# SchematicInkTime.net
KiCad netlist of a schematic drawn in EAGLE
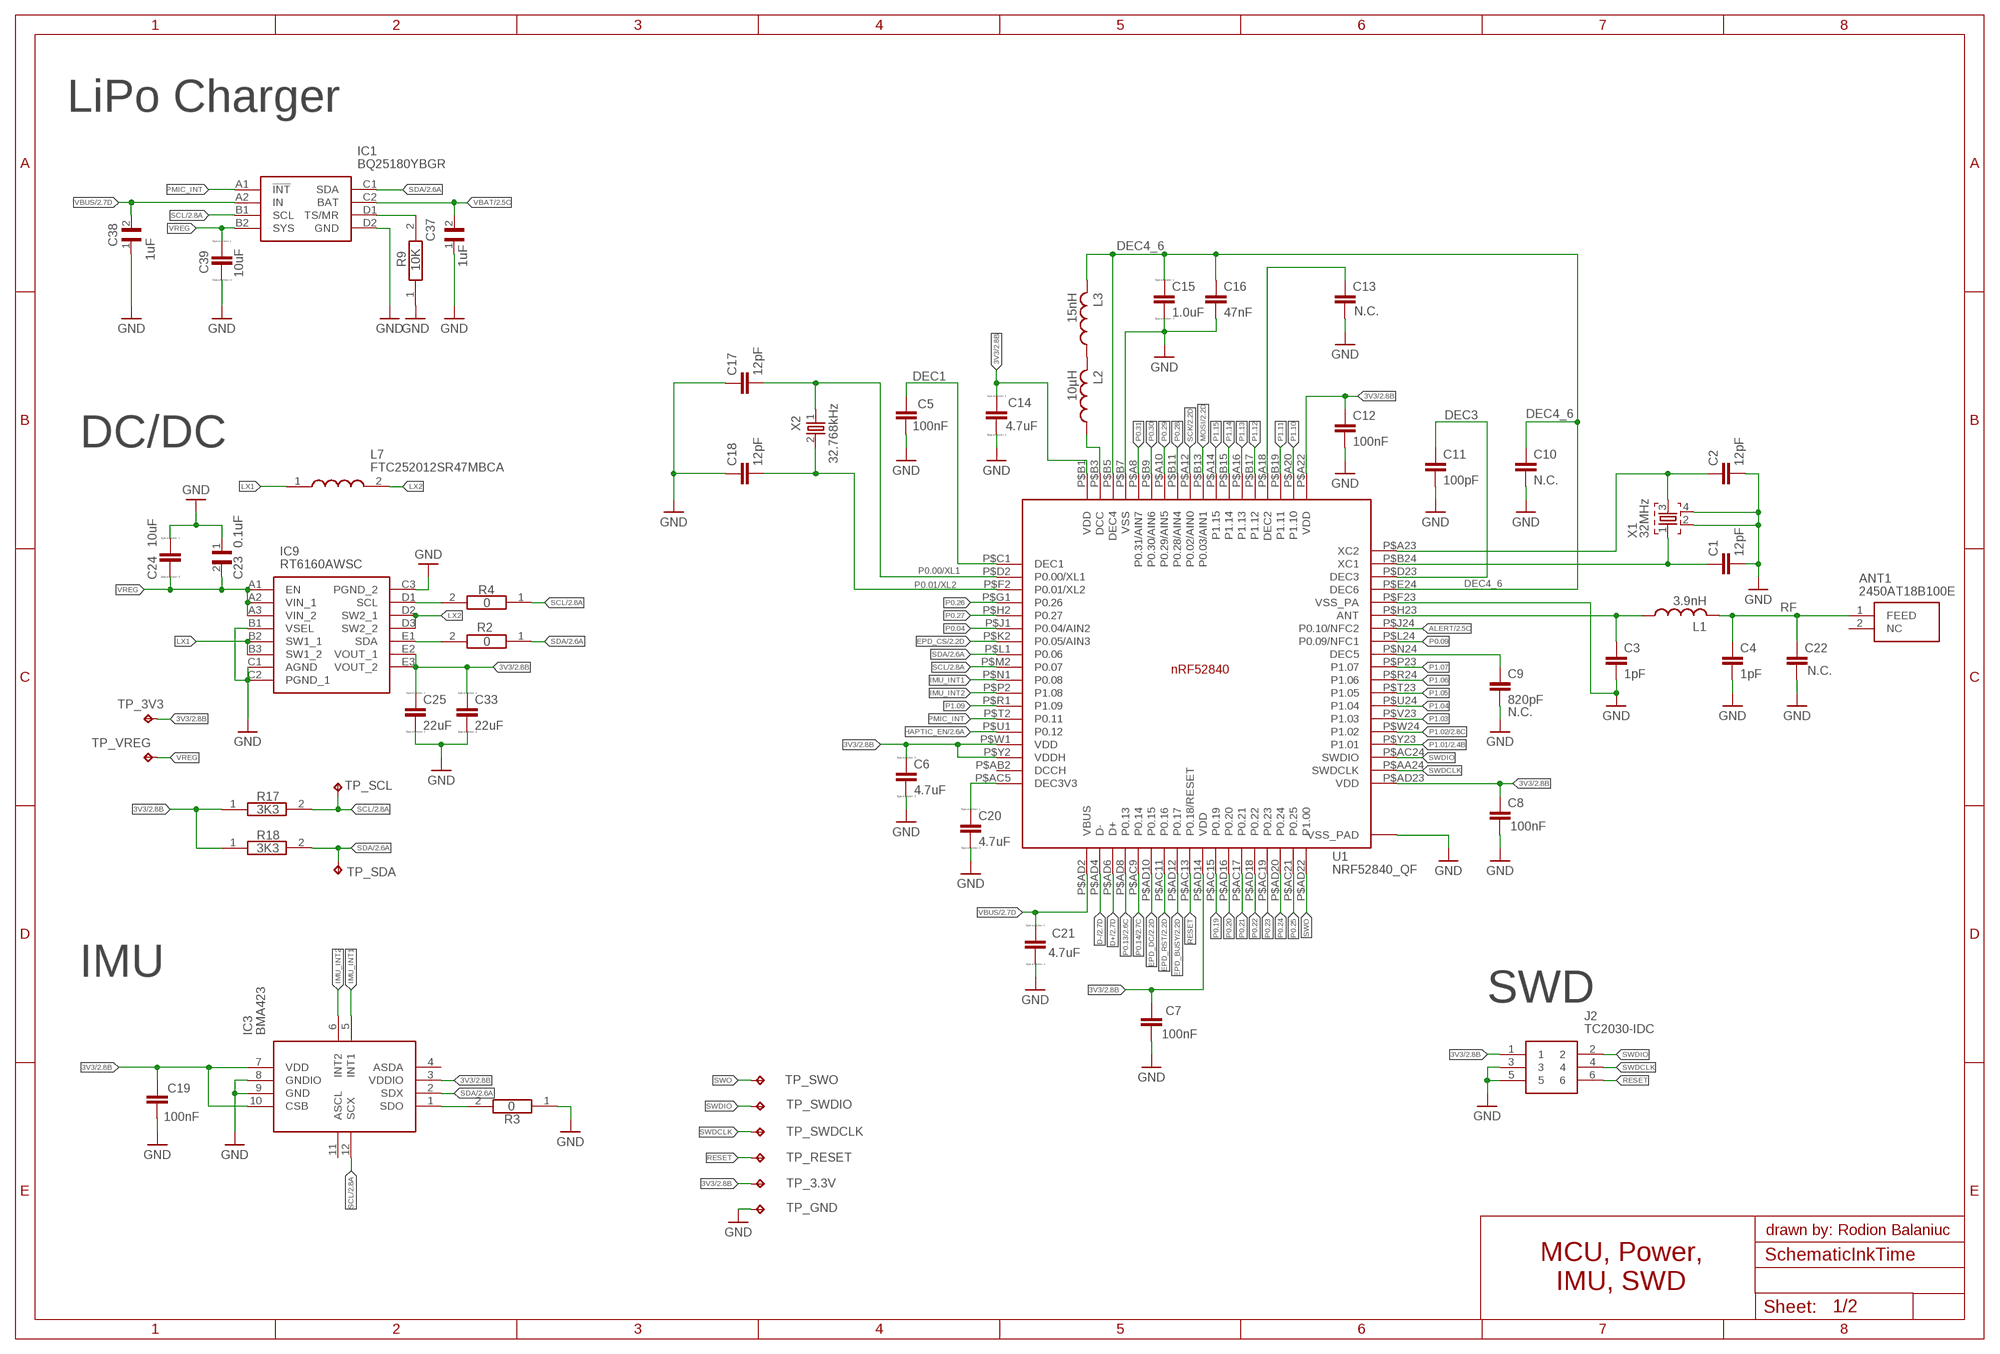
[diagram p0: schematic, sheet 1]
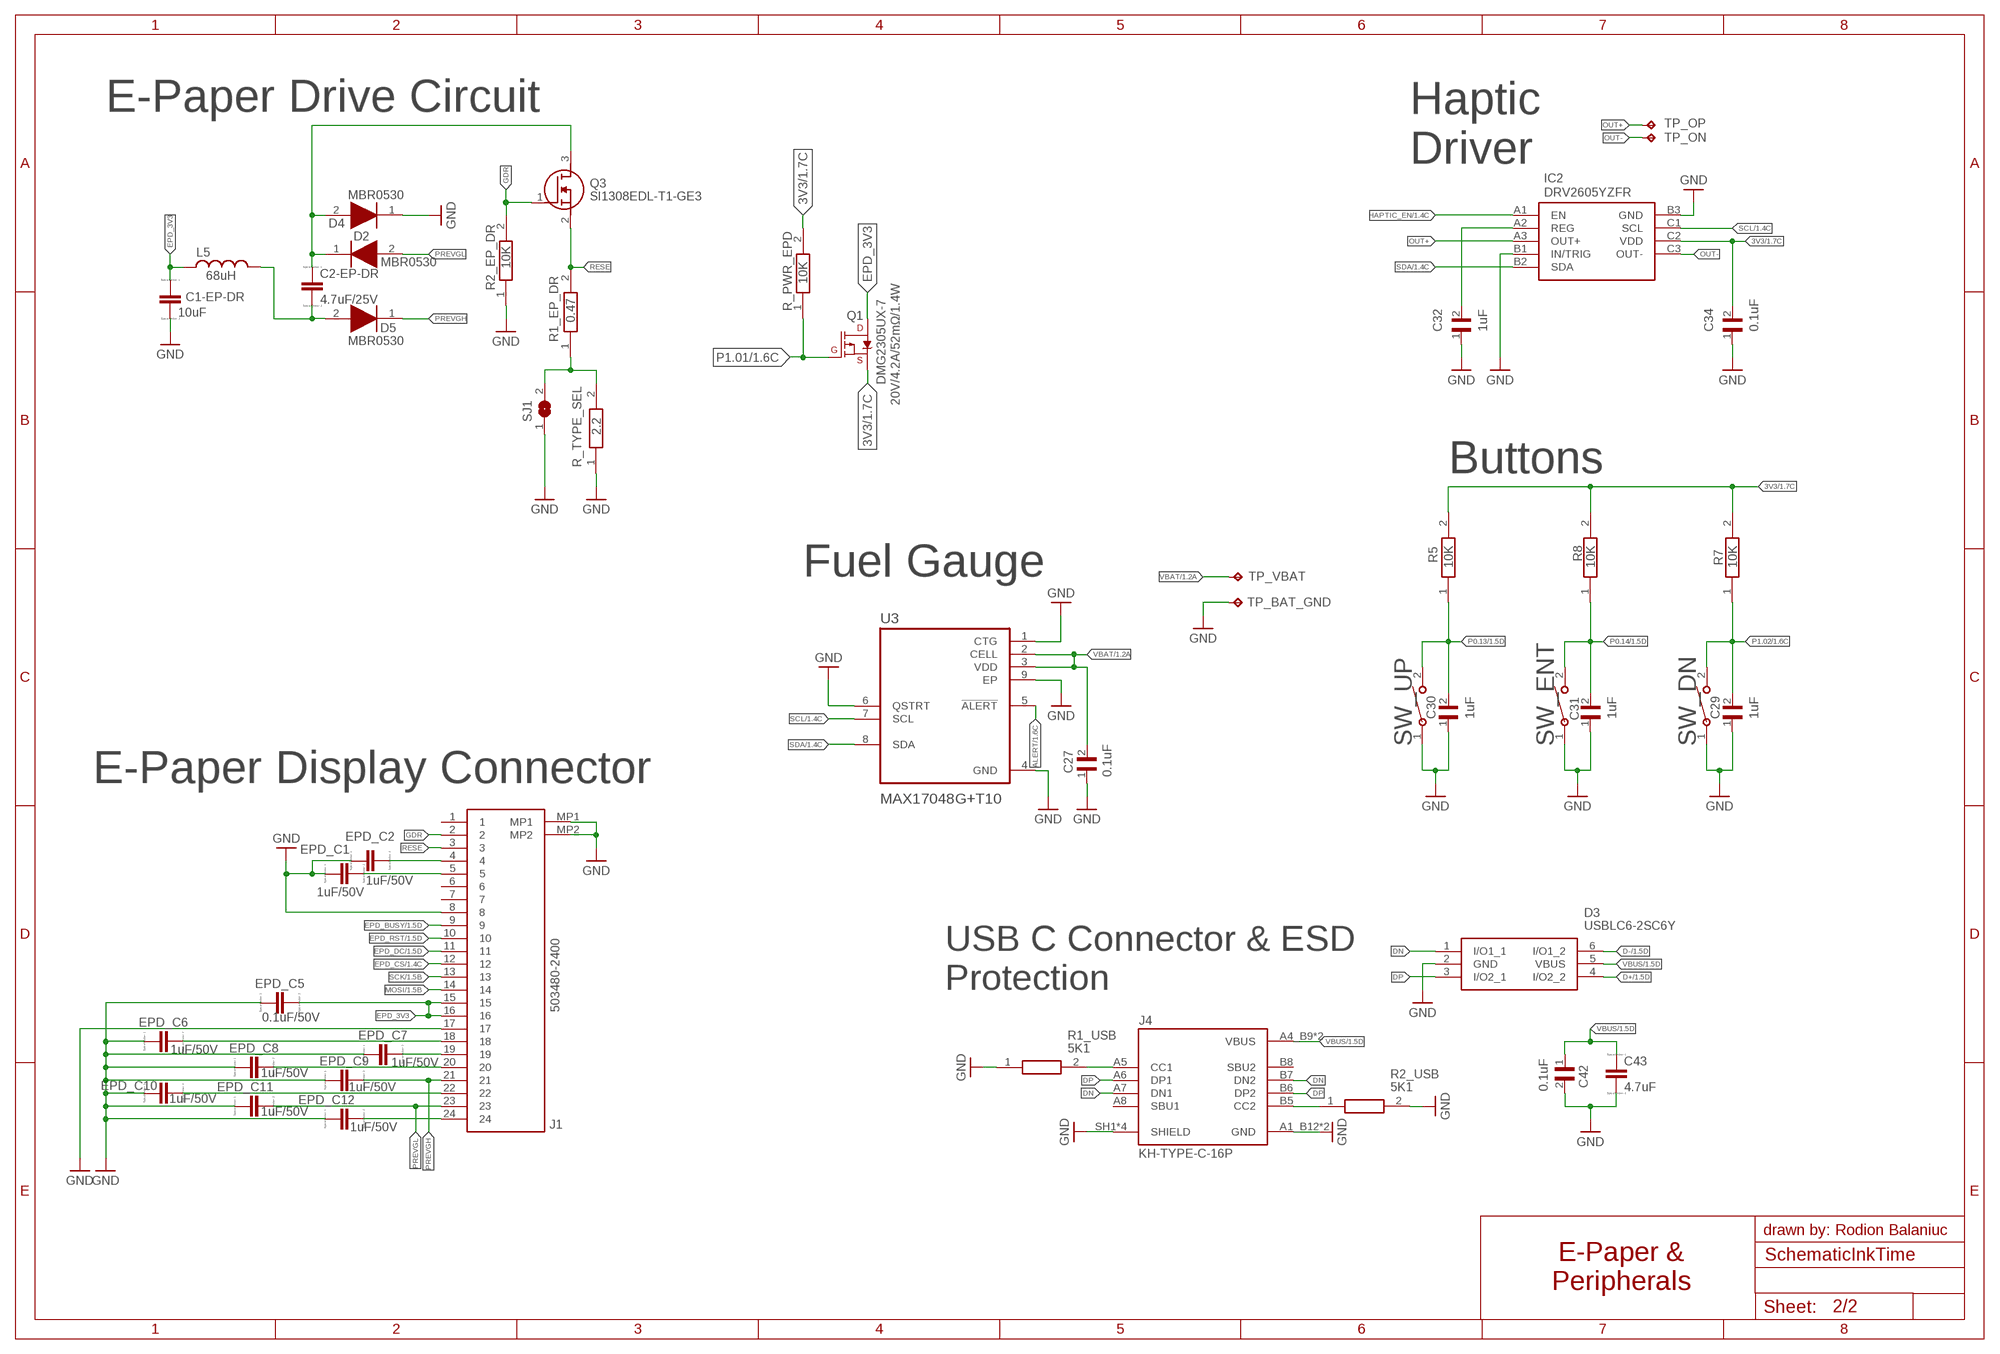
[diagram p1: schematic, sheet 2]

(export (version "E")
  (design (tool "Eeschema 10.0.6"))
  (components
    (comp (ref "C1-EP-DR")
      (value "10uF")
      (footprint "eagle-import:ESP32_C6_LIBRARY_1_ESP32_WROVER_EAGLE-LTSPICE_C0402")
      (libsource (lib "eagle-import") (part "ESP32_C6_LIBRARY_1_ESP32_WROVER_EAGLE-LTSPICE_CC0402"))
    )
    (comp (ref "C2-EP-DR")
      (value "4.7uF/25V")
      (footprint "eagle-import:ESP32_C6_LIBRARY_1_ESP32_WROVER_EAGLE-LTSPICE_C0402")
      (libsource (lib "eagle-import") (part "ESP32_C6_LIBRARY_1_ESP32_WROVER_EAGLE-LTSPICE_CC0402"))
    )
    (comp (ref "C27")
      (value "0.1uF")
      (footprint "eagle-import:GRM011R60J152KE01L_2_CAPC0201X13N")
      (fields (field (name "MF") "Murata") (field (name "MP") "GRM011R60J152KE01L"))
      (libsource (lib "eagle-import") (part "GRM011R60J152KE01L_2_GRM011R60J152KE01L"))
    )
    (comp (ref "C29")
      (value "1uF")
      (footprint "eagle-import:GRM011R60J152KE01L_2_CAPC0201X13N")
      (fields (field (name "MF") "Murata") (field (name "MP") "GRM011R60J152KE01L"))
      (libsource (lib "eagle-import") (part "GRM011R60J152KE01L_2_GRM011R60J152KE01L"))
    )
    (comp (ref "C30")
      (value "1uF")
      (footprint "eagle-import:GRM011R60J152KE01L_2_CAPC0201X13N")
      (fields (field (name "MF") "Murata") (field (name "MP") "GRM011R60J152KE01L"))
      (libsource (lib "eagle-import") (part "GRM011R60J152KE01L_2_GRM011R60J152KE01L"))
    )
    (comp (ref "C31")
      (value "1uF")
      (footprint "eagle-import:GRM011R60J152KE01L_2_CAPC0201X13N")
      (fields (field (name "MF") "Murata") (field (name "MP") "GRM011R60J152KE01L"))
      (libsource (lib "eagle-import") (part "GRM011R60J152KE01L_2_GRM011R60J152KE01L"))
    )
    (comp (ref "C32")
      (value "1uF")
      (footprint "eagle-import:GRM011R60J152KE01L_2_CAPC0201X13N")
      (fields (field (name "MF") "Murata") (field (name "MP") "GRM011R60J152KE01L"))
      (libsource (lib "eagle-import") (part "GRM011R60J152KE01L_2_GRM011R60J152KE01L"))
    )
    (comp (ref "C34")
      (value "0.1uF")
      (footprint "eagle-import:GRM011R60J152KE01L_2_CAPC0201X13N")
      (fields (field (name "MF") "Murata") (field (name "MP") "GRM011R60J152KE01L"))
      (libsource (lib "eagle-import") (part "GRM011R60J152KE01L_2_GRM011R60J152KE01L"))
    )
    (comp (ref "C42")
      (value "0.1uF")
      (footprint "eagle-import:GRM011R60J152KE01L_2_CAPC0201X13N")
      (fields (field (name "MF") "Murata") (field (name "MP") "GRM011R60J152KE01L"))
      (libsource (lib "eagle-import") (part "GRM011R60J152KE01L_2_GRM011R60J152KE01L"))
    )
    (comp (ref "C43")
      (value "4.7uF")
      (footprint "eagle-import:ESP32_C6_LIBRARY_1_ESP32_WROVER_EAGLE-LTSPICE_C0402")
      (libsource (lib "eagle-import") (part "ESP32_C6_LIBRARY_1_ESP32_WROVER_EAGLE-LTSPICE_CC0402"))
    )
    (comp (ref "D2")
      (value "MBR0530")
      (footprint "eagle-import:ESP32_C6_LIBRARY_5_SOD3716X135N")
      (fields (field (name "MF") "ON Semiconductor"))
      (libsource (lib "eagle-import") (part "ESP32_C6_LIBRARY_5_MBR0530"))
    )
    (comp (ref "D3")
      (value "USBLC6-2SC6Y")
      (footprint "eagle-import:ESP32_C6_LIBRARY_3_SOT95P280X145-6N")
      (fields (field (name "MF") "STMicroelectronics"))
      (libsource (lib "eagle-import") (part "ESP32_C6_LIBRARY_3_USBLC6-2SC6Y"))
    )
    (comp (ref "D4")
      (value "MBR0530")
      (footprint "eagle-import:ESP32_C6_LIBRARY_5_SOD3716X135N")
      (fields (field (name "MF") "ON Semiconductor"))
      (libsource (lib "eagle-import") (part "ESP32_C6_LIBRARY_5_MBR0530"))
    )
    (comp (ref "D5")
      (value "MBR0530")
      (footprint "eagle-import:ESP32_C6_LIBRARY_5_SOD3716X135N")
      (fields (field (name "MF") "ON Semiconductor"))
      (libsource (lib "eagle-import") (part "ESP32_C6_LIBRARY_5_MBR0530"))
    )
    (comp (ref "EPD_C1")
      (value "1uF/50V")
      (footprint "eagle-import:ESP32_C6_LIBRARY_1_ESP32_WROVER_EAGLE-LTSPICE_C0402")
      (libsource (lib "eagle-import") (part "ESP32_C6_LIBRARY_1_ESP32_WROVER_EAGLE-LTSPICE_CC0402"))
    )
    (comp (ref "EPD_C2")
      (value "1uF/50V")
      (footprint "eagle-import:ESP32_C6_LIBRARY_1_ESP32_WROVER_EAGLE-LTSPICE_C0402")
      (libsource (lib "eagle-import") (part "ESP32_C6_LIBRARY_1_ESP32_WROVER_EAGLE-LTSPICE_CC0402"))
    )
    (comp (ref "EPD_C5")
      (value "0.1uF/50V")
      (footprint "eagle-import:ESP32_C6_LIBRARY_1_ESP32_WROVER_EAGLE-LTSPICE_C0402")
      (libsource (lib "eagle-import") (part "ESP32_C6_LIBRARY_1_ESP32_WROVER_EAGLE-LTSPICE_CC0402"))
    )
    (comp (ref "EPD_C6")
      (value "1uF/50V")
      (footprint "eagle-import:ESP32_C6_LIBRARY_1_ESP32_WROVER_EAGLE-LTSPICE_C0402")
      (libsource (lib "eagle-import") (part "ESP32_C6_LIBRARY_1_ESP32_WROVER_EAGLE-LTSPICE_CC0402"))
    )
    (comp (ref "EPD_C7")
      (value "1uF/50V")
      (footprint "eagle-import:ESP32_C6_LIBRARY_1_ESP32_WROVER_EAGLE-LTSPICE_C0402")
      (libsource (lib "eagle-import") (part "ESP32_C6_LIBRARY_1_ESP32_WROVER_EAGLE-LTSPICE_CC0402"))
    )
    (comp (ref "EPD_C8")
      (value "1uF/50V")
      (footprint "eagle-import:ESP32_C6_LIBRARY_1_ESP32_WROVER_EAGLE-LTSPICE_C0402")
      (libsource (lib "eagle-import") (part "ESP32_C6_LIBRARY_1_ESP32_WROVER_EAGLE-LTSPICE_CC0402"))
    )
    (comp (ref "EPD_C9")
      (value "1uF/50V")
      (footprint "eagle-import:ESP32_C6_LIBRARY_1_ESP32_WROVER_EAGLE-LTSPICE_C0402")
      (libsource (lib "eagle-import") (part "ESP32_C6_LIBRARY_1_ESP32_WROVER_EAGLE-LTSPICE_CC0402"))
    )
    (comp (ref "EPD_C10")
      (value "1uF/50V")
      (footprint "eagle-import:ESP32_C6_LIBRARY_1_ESP32_WROVER_EAGLE-LTSPICE_C0402")
      (libsource (lib "eagle-import") (part "ESP32_C6_LIBRARY_1_ESP32_WROVER_EAGLE-LTSPICE_CC0402"))
    )
    (comp (ref "EPD_C11")
      (value "1uF/50V")
      (footprint "eagle-import:ESP32_C6_LIBRARY_1_ESP32_WROVER_EAGLE-LTSPICE_C0402")
      (libsource (lib "eagle-import") (part "ESP32_C6_LIBRARY_1_ESP32_WROVER_EAGLE-LTSPICE_CC0402"))
    )
    (comp (ref "EPD_C12")
      (value "1uF/50V")
      (footprint "eagle-import:ESP32_C6_LIBRARY_1_ESP32_WROVER_EAGLE-LTSPICE_C0402")
      (libsource (lib "eagle-import") (part "ESP32_C6_LIBRARY_1_ESP32_WROVER_EAGLE-LTSPICE_CC0402"))
    )
    (comp (ref "IC2")
      (value "DRV2605YZFR")
      (footprint "eagle-import:DRV2605YZFR_BGA9C50P3X3_144X144X62")
      (libsource (lib "eagle-import") (part "DRV2605YZFR_DRV2605YZFR"))
    )
    (comp (ref "J1")
      (value "503480-2400")
      (footprint "eagle-import:503480-2400_5034802400")
      (fields (field (name "MOUSER_PART_NUMBER") "538-503480-2400"))
      (libsource (lib "eagle-import") (part "503480-2400_503480-2400"))
    )
    (comp (ref "J4")
      (value "KH-TYPE-C-16P")
      (footprint "eagle-import:KH-TYPE-C-16P_KINGHELM_KH-TYPE-C-16P")
      (fields (field (name "MF") "kinghelm"))
      (libsource (lib "eagle-import") (part "KH-TYPE-C-16P_KH-TYPE-C-16P"))
    )
    (comp (ref "L5")
      (value "68uH")
      (footprint "eagle-import:NORDIC_NRF_2_RESC0402_L")
      (libsource (lib "eagle-import") (part "NORDIC_NRF_2_INDUCTOR_0402_L"))
    )
    (comp (ref "Q1")
      (value "20V/4.2A/52mΩ/1.4W")
      (footprint "eagle-import:ESP32_C6_LIBRARY_4_ESP32_C6_LIBRARY_4_ESP32_C6_LIBRARY_4_ESP32_C6_LIBRARY_4_ESP32_WROVER_SPARKFUN-DISCRETESEMI_SOT23-3")
      (fields (field (name "ATTR") "DMG2305UX-7 "))
      (libsource (lib "eagle-import") (part "ESP32_C6_LIBRARY_4_ESP32_WROVER_SPARKFUN-DISCRETESEMI_MOSFET_PCH-DMG2305UX-7"))
    )
    (comp (ref "Q3")
      (value "SI1308EDL-T1-GE3")
      (footprint "eagle-import:ESP32_C6_LIBRARY_6_SOT65P210X110-3N")
      (fields (field (name "MF") "Vishay Siliconix"))
      (libsource (lib "eagle-import") (part "ESP32_C6_LIBRARY_6_SI1308EDL-T1-GE3"))
    )
    (comp (ref "R1_EP_DR")
      (value "0.47")
      (footprint "eagle-import:CPF0201D7K68C1_0201")
      (libsource (lib "eagle-import") (part "CPF0201D7K68C1_CPF0201D7K68C1"))
    )
    (comp (ref "R1_USB")
      (value "5K1")
      (footprint "eagle-import:CPF0201D7K68C1_0201")
      (libsource (lib "eagle-import") (part "CPF0201D7K68C1_CPF0201D7K68C1"))
    )
    (comp (ref "R2_EP_DR")
      (value "10K")
      (footprint "eagle-import:CPF0201D7K68C1_0201")
      (libsource (lib "eagle-import") (part "CPF0201D7K68C1_CPF0201D7K68C1"))
    )
    (comp (ref "R2_USB")
      (value "5K1")
      (footprint "eagle-import:CPF0201D7K68C1_0201")
      (libsource (lib "eagle-import") (part "CPF0201D7K68C1_CPF0201D7K68C1"))
    )
    (comp (ref "R5")
      (value "10K")
      (footprint "eagle-import:CPF0201D7K68C1_0201")
      (libsource (lib "eagle-import") (part "CPF0201D7K68C1_CPF0201D7K68C1"))
    )
    (comp (ref "R7")
      (value "10K")
      (footprint "eagle-import:CPF0201D7K68C1_0201")
      (libsource (lib "eagle-import") (part "CPF0201D7K68C1_CPF0201D7K68C1"))
    )
    (comp (ref "R8")
      (value "10K")
      (footprint "eagle-import:CPF0201D7K68C1_0201")
      (libsource (lib "eagle-import") (part "CPF0201D7K68C1_CPF0201D7K68C1"))
    )
    (comp (ref "R_PWR_EPD")
      (value "10K")
      (footprint "eagle-import:CPF0201D7K68C1_0201")
      (libsource (lib "eagle-import") (part "CPF0201D7K68C1_CPF0201D7K68C1"))
    )
    (comp (ref "R_TYPE_SEL")
      (value "2.2")
      (footprint "eagle-import:CPF0201D7K68C1_0201")
      (libsource (lib "eagle-import") (part "CPF0201D7K68C1_CPF0201D7K68C1"))
    )
    (comp (ref "SJ1")
      (value "ESP32_C6_LIBRARY_7_JUMPER_SJ")
      (footprint "eagle-import:ESP32_C6_LIBRARY_7_JUMPER_SJ")
      (libsource (lib "eagle-import") (part "ESP32_C6_LIBRARY_7_JUMPER_SJ"))
    )
    (comp (ref "SW_DN")
      (value "2025-10-22_07-23-44_LIBRARY_EVP-AKE31ASW_EVP-AKE31A_PAN")
      (footprint "eagle-import:2025-10-22_07-23-44_LIBRARY_SW_EVP-AKE31A_PAN")
      (fields
        (field (name "MANUFACTURER_PART_NUMBER") "EVP-AKE31A")
        (field (name "COPYRIGHT") "Copyright (C) 2025 Ultra Librarian. All rights reserved.")
      )
      (libsource (lib "eagle-import") (part "2025-10-22_07-23-44_LIBRARY_EVP-AKE31ASW_EVP-AKE31A_PAN"))
    )
    (comp (ref "SW_ENT")
      (value "2025-10-22_07-23-44_LIBRARY_EVP-AKE31ASW_EVP-AKE31A_PAN")
      (footprint "eagle-import:2025-10-22_07-23-44_LIBRARY_SW_EVP-AKE31A_PAN")
      (fields
        (field (name "MANUFACTURER_PART_NUMBER") "EVP-AKE31A")
        (field (name "COPYRIGHT") "Copyright (C) 2025 Ultra Librarian. All rights reserved.")
      )
      (libsource (lib "eagle-import") (part "2025-10-22_07-23-44_LIBRARY_EVP-AKE31ASW_EVP-AKE31A_PAN"))
    )
    (comp (ref "SW_UP")
      (value "2025-10-22_07-23-44_LIBRARY_EVP-AKE31ASW_EVP-AKE31A_PAN")
      (footprint "eagle-import:2025-10-22_07-23-44_LIBRARY_SW_EVP-AKE31A_PAN")
      (fields
        (field (name "MANUFACTURER_PART_NUMBER") "EVP-AKE31A")
        (field (name "COPYRIGHT") "Copyright (C) 2025 Ultra Librarian. All rights reserved.")
      )
      (libsource (lib "eagle-import") (part "2025-10-22_07-23-44_LIBRARY_EVP-AKE31ASW_EVP-AKE31A_PAN"))
    )
    (comp (ref "TP_BAT_GND")
      (value "HECTOR_WATCH_1_TPTP20R")
      (footprint "eagle-import:HECTOR_WATCH_1_TP20R")
      (libsource (lib "eagle-import") (part "HECTOR_WATCH_1_TPTP20R"))
    )
    (comp (ref "TP_ON")
      (value "HECTOR_WATCH_1_TPTP20R")
      (footprint "eagle-import:HECTOR_WATCH_1_TP20R")
      (libsource (lib "eagle-import") (part "HECTOR_WATCH_1_TPTP20R"))
    )
    (comp (ref "TP_OP")
      (value "HECTOR_WATCH_1_TPTP20R")
      (footprint "eagle-import:HECTOR_WATCH_1_TP20R")
      (libsource (lib "eagle-import") (part "HECTOR_WATCH_1_TPTP20R"))
    )
    (comp (ref "TP_VBAT")
      (value "HECTOR_WATCH_1_TPTP20R")
      (footprint "eagle-import:HECTOR_WATCH_1_TP20R")
      (libsource (lib "eagle-import") (part "HECTOR_WATCH_1_TPTP20R"))
    )
    (comp (ref "U3")
      (value "MAX17048G+T10")
      (footprint "eagle-import:ESP32_C6_LIBRARY_SON50P200X200X80-9N")
      (fields (field (name "MF") "Analog Devices"))
      (libsource (lib "eagle-import") (part "ESP32_C6_LIBRARY_MAX17048G+T10"))
    )
    (comp (ref "ANT1")
      (value "2450AT18B100E")
      (footprint "eagle-import:2450AT18B100E_ANTC3216X140N")
      (fields (field (name "MOUSER_PART_NUMBER") "609-2450AT18B100E"))
      (libsource (lib "eagle-import") (part "2450AT18B100E_2450AT18B100E"))
    )
    (comp (ref "C1")
      (value "12pF")
      (footprint "eagle-import:NORDIC_NRF_3_RESC0201_L")
      (libsource (lib "eagle-import") (part "NORDIC_NRF_3_CAPACITOR_0201_L"))
    )
    (comp (ref "C2")
      (value "12pF")
      (footprint "eagle-import:NORDIC_NRF_3_RESC0201_L")
      (libsource (lib "eagle-import") (part "NORDIC_NRF_3_CAPACITOR_0201_L"))
    )
    (comp (ref "C3")
      (value "1pF")
      (footprint "eagle-import:NORDIC_NRF_3_RESC0201_L")
      (libsource (lib "eagle-import") (part "NORDIC_NRF_3_CAPACITOR_0201_L"))
    )
    (comp (ref "C4")
      (value "1pF")
      (footprint "eagle-import:NORDIC_NRF_3_RESC0201_L")
      (libsource (lib "eagle-import") (part "NORDIC_NRF_3_CAPACITOR_0201_L"))
    )
    (comp (ref "C5")
      (value "100nF")
      (footprint "eagle-import:NORDIC_NRF_3_RESC0201_L")
      (libsource (lib "eagle-import") (part "NORDIC_NRF_3_CAPACITOR_0201_L"))
    )
    (comp (ref "C6")
      (value "4.7uF")
      (footprint "eagle-import:ESP32_C6_LIBRARY_1_ESP32_WROVER_EAGLE-LTSPICE_C0402")
      (libsource (lib "eagle-import") (part "ESP32_C6_LIBRARY_1_ESP32_WROVER_EAGLE-LTSPICE_CC0402"))
    )
    (comp (ref "C7")
      (value "100nF")
      (footprint "eagle-import:NORDIC_NRF_3_RESC0201_L")
      (libsource (lib "eagle-import") (part "NORDIC_NRF_3_CAPACITOR_0201_L"))
    )
    (comp (ref "C8")
      (value "100nF")
      (footprint "eagle-import:NORDIC_NRF_3_RESC0201_L")
      (libsource (lib "eagle-import") (part "NORDIC_NRF_3_CAPACITOR_0201_L"))
    )
    (comp (ref "C9")
      (value "820pF")
      (footprint "eagle-import:NORDIC_NRF_3_RESC0201_L")
      (fields (field (name "DNP") "N.C."))
      (libsource (lib "eagle-import") (part "NORDIC_NRF_3_CAPACITOR_0201_L"))
    )
    (comp (ref "C10")
      (value "N.C.")
      (footprint "eagle-import:NORDIC_NRF_3_RESC0201_L")
      (fields (field (name "DNP") "N.C."))
      (libsource (lib "eagle-import") (part "NORDIC_NRF_3_CAPACITOR_0201_L"))
    )
    (comp (ref "C11")
      (value "100pF")
      (footprint "eagle-import:NORDIC_NRF_3_RESC0201_L")
      (libsource (lib "eagle-import") (part "NORDIC_NRF_3_CAPACITOR_0201_L"))
    )
    (comp (ref "C12")
      (value "100nF")
      (footprint "eagle-import:NORDIC_NRF_3_RESC0201_L")
      (libsource (lib "eagle-import") (part "NORDIC_NRF_3_CAPACITOR_0201_L"))
    )
    (comp (ref "C13")
      (value "N.C.")
      (footprint "eagle-import:NORDIC_NRF_3_RESC0201_L")
      (fields (field (name "DNP") "N.C."))
      (libsource (lib "eagle-import") (part "NORDIC_NRF_3_CAPACITOR_0201_L"))
    )
    (comp (ref "C14")
      (value "4.7uF")
      (footprint "eagle-import:ESP32_C6_LIBRARY_1_ESP32_WROVER_EAGLE-LTSPICE_C0402")
      (libsource (lib "eagle-import") (part "ESP32_C6_LIBRARY_1_ESP32_WROVER_EAGLE-LTSPICE_CC0402"))
    )
    (comp (ref "C15")
      (value "1.0uF")
      (footprint "eagle-import:ESP32_C6_LIBRARY_1_ESP32_WROVER_EAGLE-LTSPICE_C0402")
      (libsource (lib "eagle-import") (part "ESP32_C6_LIBRARY_1_ESP32_WROVER_EAGLE-LTSPICE_CC0402"))
    )
    (comp (ref "C16")
      (value "47nF")
      (footprint "eagle-import:NORDIC_NRF_3_RESC0201_L")
      (libsource (lib "eagle-import") (part "NORDIC_NRF_3_CAPACITOR_0201_L"))
    )
    (comp (ref "C17")
      (value "12pF")
      (footprint "eagle-import:NORDIC_NRF_3_RESC0201_L")
      (libsource (lib "eagle-import") (part "NORDIC_NRF_3_CAPACITOR_0201_L"))
    )
    (comp (ref "C18")
      (value "12pF")
      (footprint "eagle-import:NORDIC_NRF_3_RESC0201_L")
      (libsource (lib "eagle-import") (part "NORDIC_NRF_3_CAPACITOR_0201_L"))
    )
    (comp (ref "C19")
      (value "100nF")
      (footprint "eagle-import:NORDIC_NRF_3_RESC0201_L")
      (libsource (lib "eagle-import") (part "NORDIC_NRF_3_CAPACITOR_0201_L"))
    )
    (comp (ref "C20")
      (value "4.7uF")
      (footprint "eagle-import:ESP32_C6_LIBRARY_1_ESP32_WROVER_EAGLE-LTSPICE_C0402")
      (libsource (lib "eagle-import") (part "ESP32_C6_LIBRARY_1_ESP32_WROVER_EAGLE-LTSPICE_CC0402"))
    )
    (comp (ref "C21")
      (value "4.7uF")
      (footprint "eagle-import:ESP32_C6_LIBRARY_1_ESP32_WROVER_EAGLE-LTSPICE_C0402")
      (libsource (lib "eagle-import") (part "ESP32_C6_LIBRARY_1_ESP32_WROVER_EAGLE-LTSPICE_CC0402"))
    )
    (comp (ref "C22")
      (value "N.C.")
      (footprint "eagle-import:NORDIC_NRF_3_RESC0201_L")
      (fields (field (name "DNP") "N.C."))
      (libsource (lib "eagle-import") (part "NORDIC_NRF_3_CAPACITOR_0201_L"))
    )
    (comp (ref "C23")
      (value "0.1uF")
      (footprint "eagle-import:GRM011R60J152KE01L_2_CAPC0201X13N")
      (fields (field (name "MF") "Murata") (field (name "MP") "GRM011R60J152KE01L"))
      (libsource (lib "eagle-import") (part "GRM011R60J152KE01L_2_GRM011R60J152KE01L"))
    )
    (comp (ref "C24")
      (value "10uF")
      (footprint "eagle-import:ESP32_C6_LIBRARY_1_ESP32_WROVER_EAGLE-LTSPICE_C0402")
      (libsource (lib "eagle-import") (part "ESP32_C6_LIBRARY_1_ESP32_WROVER_EAGLE-LTSPICE_CC0402"))
    )
    (comp (ref "C25")
      (value "22uF")
      (footprint "eagle-import:ESP32_C6_LIBRARY_1_ESP32_WROVER_EAGLE-LTSPICE_C0402")
      (libsource (lib "eagle-import") (part "ESP32_C6_LIBRARY_1_ESP32_WROVER_EAGLE-LTSPICE_CC0402"))
    )
    (comp (ref "C33")
      (value "22uF")
      (footprint "eagle-import:ESP32_C6_LIBRARY_1_ESP32_WROVER_EAGLE-LTSPICE_C0402")
      (libsource (lib "eagle-import") (part "ESP32_C6_LIBRARY_1_ESP32_WROVER_EAGLE-LTSPICE_CC0402"))
    )
    (comp (ref "C37")
      (value "1uF")
      (footprint "eagle-import:GRM011R60J152KE01L_2_CAPC0201X13N")
      (fields (field (name "MF") "Murata") (field (name "MP") "GRM011R60J152KE01L"))
      (libsource (lib "eagle-import") (part "GRM011R60J152KE01L_2_GRM011R60J152KE01L"))
    )
    (comp (ref "C38")
      (value "1uF")
      (footprint "eagle-import:GRM011R60J152KE01L_2_CAPC0201X13N")
      (fields (field (name "MF") "Murata") (field (name "MP") "GRM011R60J152KE01L"))
      (libsource (lib "eagle-import") (part "GRM011R60J152KE01L_2_GRM011R60J152KE01L"))
    )
    (comp (ref "C39")
      (value "10uF")
      (footprint "eagle-import:ESP32_C6_LIBRARY_1_ESP32_WROVER_EAGLE-LTSPICE_C0402")
      (libsource (lib "eagle-import") (part "ESP32_C6_LIBRARY_1_ESP32_WROVER_EAGLE-LTSPICE_CC0402"))
    )
    (comp (ref "IC1")
      (value "BQ25180YBGR")
      (footprint "eagle-import:BQ25180YBGR_BGA8C40P2X4_100X155X50")
      (fields (field (name "MOUSER_PART_NUMBER") "595-BQ25180YBGR"))
      (libsource (lib "eagle-import") (part "BQ25180YBGR_BQ25180YBGR"))
    )
    (comp (ref "IC3")
      (value "BMA423")
      (footprint "eagle-import:BMA423_BMA423")
      (fields (field (name "MOUSER_PART_NUMBER") "262-BMA423"))
      (libsource (lib "eagle-import") (part "BMA423_BMA423"))
    )
    (comp (ref "IC9")
      (value "RT6160AWSC")
      (footprint "eagle-import:RT6160AWSC_BGA15C40P3X5_140X230X60")
      (fields (field (name "MOUSER_PART_NUMBER") "835-RT6160AWSC"))
      (libsource (lib "eagle-import") (part "RT6160AWSC_RT6160AWSC"))
    )
    (comp (ref "J2")
      (value "TC2030-IDC")
      (footprint "eagle-import:TC2030-IDC_TC2030IDC")
      (libsource (lib "eagle-import") (part "TC2030-IDC_TC2030-IDC"))
    )
    (comp (ref "L1")
      (value "3.9nH")
      (footprint "eagle-import:NORDIC_NRF_2_RESC0402_L")
      (libsource (lib "eagle-import") (part "NORDIC_NRF_2_INDUCTOR_0402_L"))
    )
    (comp (ref "L2")
      (value "10µH")
      (footprint "eagle-import:NORDIC_NRF_2_RESC0402_L")
      (libsource (lib "eagle-import") (part "NORDIC_NRF_2_INDUCTOR_0402_L"))
    )
    (comp (ref "L3")
      (value "15nH")
      (footprint "eagle-import:NORDIC_NRF_2_RESC0402_L")
      (libsource (lib "eagle-import") (part "NORDIC_NRF_2_INDUCTOR_0402_L"))
    )
    (comp (ref "L7")
      (value "FTC252012SR47MBCA")
      (footprint "eagle-import:MLP2016SR47MT0S1_INDC2016X100N")
      (libsource (lib "eagle-import") (part "MLP2016SR47MT0S1_FTC252012SR47MBCA"))
    )
    (comp (ref "R2")
      (value "0")
      (footprint "eagle-import:CPF0201D7K68C1_0201")
      (libsource (lib "eagle-import") (part "CPF0201D7K68C1_CPF0201D7K68C1"))
    )
    (comp (ref "R3")
      (value "0")
      (footprint "eagle-import:CPF0201D7K68C1_0201")
      (libsource (lib "eagle-import") (part "CPF0201D7K68C1_CPF0201D7K68C1"))
    )
    (comp (ref "R4")
      (value "0")
      (footprint "eagle-import:CPF0201D7K68C1_0201")
      (libsource (lib "eagle-import") (part "CPF0201D7K68C1_CPF0201D7K68C1"))
    )
    (comp (ref "R9")
      (value "10K")
      (footprint "eagle-import:CPF0201D7K68C1_0201")
      (libsource (lib "eagle-import") (part "CPF0201D7K68C1_CPF0201D7K68C1"))
    )
    (comp (ref "R17")
      (value "3K3")
      (footprint "eagle-import:ERA-1AEB3401C_0201")
      (libsource (lib "eagle-import") (part "ERA-1AEB3401C_CPF0201D7K68C1"))
    )
    (comp (ref "R18")
      (value "3K3")
      (footprint "eagle-import:ERA-1AEB3401C_0201")
      (libsource (lib "eagle-import") (part "ERA-1AEB3401C_CPF0201D7K68C1"))
    )
    (comp (ref "TP_3.3V")
      (value "HECTOR_WATCH_1_TPTP20R")
      (footprint "eagle-import:HECTOR_WATCH_1_TP20R")
      (libsource (lib "eagle-import") (part "HECTOR_WATCH_1_TPTP20R"))
    )
    (comp (ref "TP_3V3")
      (value "HECTOR_WATCH_1_TPTP20R")
      (footprint "eagle-import:HECTOR_WATCH_1_TP20R")
      (libsource (lib "eagle-import") (part "HECTOR_WATCH_1_TPTP20R"))
    )
    (comp (ref "TP_GND")
      (value "HECTOR_WATCH_1_TPTP20R")
      (footprint "eagle-import:HECTOR_WATCH_1_TP20R")
      (libsource (lib "eagle-import") (part "HECTOR_WATCH_1_TPTP20R"))
    )
    (comp (ref "TP_RESET")
      (value "HECTOR_WATCH_1_TPTP20R")
      (footprint "eagle-import:HECTOR_WATCH_1_TP20R")
      (libsource (lib "eagle-import") (part "HECTOR_WATCH_1_TPTP20R"))
    )
    (comp (ref "TP_SCL")
      (value "HECTOR_WATCH_1_TPTP20R")
      (footprint "eagle-import:HECTOR_WATCH_1_TP20R")
      (libsource (lib "eagle-import") (part "HECTOR_WATCH_1_TPTP20R"))
    )
    (comp (ref "TP_SDA")
      (value "HECTOR_WATCH_1_TPTP20R")
      (footprint "eagle-import:HECTOR_WATCH_1_TP20R")
      (libsource (lib "eagle-import") (part "HECTOR_WATCH_1_TPTP20R"))
    )
    (comp (ref "TP_SWDCLK")
      (value "HECTOR_WATCH_1_TPTP20R")
      (footprint "eagle-import:HECTOR_WATCH_1_TP20R")
      (libsource (lib "eagle-import") (part "HECTOR_WATCH_1_TPTP20R"))
    )
    (comp (ref "TP_SWDIO")
      (value "HECTOR_WATCH_1_TPTP20R")
      (footprint "eagle-import:HECTOR_WATCH_1_TP20R")
      (libsource (lib "eagle-import") (part "HECTOR_WATCH_1_TPTP20R"))
    )
    (comp (ref "TP_SWO")
      (value "HECTOR_WATCH_1_TPTP20R")
      (footprint "eagle-import:HECTOR_WATCH_1_TP20R")
      (libsource (lib "eagle-import") (part "HECTOR_WATCH_1_TPTP20R"))
    )
    (comp (ref "TP_VREG")
      (value "HECTOR_WATCH_1_TPTP20R")
      (footprint "eagle-import:HECTOR_WATCH_1_TP20R")
      (libsource (lib "eagle-import") (part "HECTOR_WATCH_1_TPTP20R"))
    )
    (comp (ref "U1")
      (value "NRF52840_QF")
      (footprint "eagle-import:NORDIC_NRF_4_AQFN50P700X700X85_HS-74N")
      (libsource (lib "eagle-import") (part "NORDIC_NRF_4_NRF52840_QF"))
    )
    (comp (ref "X1")
      (value "32MHz")
      (footprint "eagle-import:NORDIC_NRF_BT-XTAL_2016_N")
      (libsource (lib "eagle-import") (part "NORDIC_NRF_XTAL_32MHZ"))
    )
    (comp (ref "X2")
      (value "32.768kHz")
      (footprint "eagle-import:NORDIC_NRF_1_XTAL_3215_N")
      (libsource (lib "eagle-import") (part "NORDIC_NRF_1_XTAL_32KHZ"))
    )
  )
  (nets
    (net (code "1") (name "3V3") (class "Default")
      (node (ref "C12") (pin "1") (pinfunction "1_1") (pintype "passive"))
      (node (ref "C14") (pin "1") (pinfunction "1_1") (pintype "passive"))
      (node (ref "C19") (pin "1") (pinfunction "1_1") (pintype "passive"))
      (node (ref "C25") (pin "1") (pinfunction "1_1") (pintype "passive"))
      (node (ref "C33") (pin "1") (pinfunction "1_1") (pintype "passive"))
      (node (ref "C34") (pin "2") (pinfunction "2_2") (pintype "passive"))
      (node (ref "C6") (pin "1") (pinfunction "1_1") (pintype "passive"))
      (node (ref "C7") (pin "1") (pinfunction "1_1") (pintype "passive"))
      (node (ref "C8") (pin "1") (pinfunction "1_1") (pintype "passive"))
      (node (ref "IC2") (pin "C2") (pinfunction "VDD_C2") (pintype "bidirectional"))
      (node (ref "IC3") (pin "10") (pinfunction "CSB_10") (pintype "bidirectional"))
      (node (ref "IC3") (pin "3") (pinfunction "VDDIO_3") (pintype "bidirectional"))
      (node (ref "IC3") (pin "7") (pinfunction "VDD_7") (pintype "bidirectional"))
      (node (ref "IC9") (pin "E2") (pinfunction "VOUT_1_E2") (pintype "bidirectional"))
      (node (ref "IC9") (pin "E3") (pinfunction "VOUT_2_E3") (pintype "bidirectional"))
      (node (ref "J2") (pin "1") (pinfunction "1_1") (pintype "bidirectional"))
      (node (ref "Q1") (pin "2") (pinfunction "S_2") (pintype "bidirectional"))
      (node (ref "R17") (pin "1") (pinfunction "1_1") (pintype "bidirectional"))
      (node (ref "R18") (pin "1") (pinfunction "1_1") (pintype "bidirectional"))
      (node (ref "R5") (pin "2") (pinfunction "2_2") (pintype "bidirectional"))
      (node (ref "R7") (pin "2") (pinfunction "2_2") (pintype "bidirectional"))
      (node (ref "R8") (pin "2") (pinfunction "2_2") (pintype "bidirectional"))
      (node (ref "R_PWR_EPD") (pin "2") (pinfunction "2_2") (pintype "bidirectional"))
      (node (ref "TP_3.3V") (pin "TP") (pinfunction "TP_TP") (pintype "input"))
      (node (ref "TP_3V3") (pin "TP") (pinfunction "TP_TP") (pintype "input"))
      (node (ref "U1") (pin "P$A22") (pinfunction "VDD_P$A22") (pintype "power_in"))
      (node (ref "U1") (pin "P$AD14") (pinfunction "VDD_P$AD14") (pintype "power_in"))
      (node (ref "U1") (pin "P$AD23") (pinfunction "VDD_P$AD23") (pintype "power_in"))
      (node (ref "U1") (pin "P$B1") (pinfunction "VDD_P$B1") (pintype "power_in"))
      (node (ref "U1") (pin "P$W1") (pinfunction "VDD_P$W1") (pintype "power_in"))
      (node (ref "U1") (pin "P$Y2") (pinfunction "VDDH_P$Y2") (pintype "power_in"))
    )
    (net (code "2") (name "ALERT") (class "Default")
      (node (ref "U1") (pin "P$J24") (pinfunction "P0.10/NFC2_P$J24") (pintype "bidirectional"))
      (node (ref "U3") (pin "5") (pinfunction "~{ALERT}_5") (pintype "output"))
    )
    (net (code "3") (name "D+") (class "Default")
      (node (ref "D3") (pin "4") (pinfunction "I/O2_2_4") (pintype "bidirectional"))
      (node (ref "U1") (pin "P$AD6") (pinfunction "D+_P$AD6") (pintype "bidirectional"))
    )
    (net (code "4") (name "D-") (class "Default")
      (node (ref "D3") (pin "6") (pinfunction "I/O1_2_6") (pintype "bidirectional"))
      (node (ref "U1") (pin "P$AD4") (pinfunction "D-_P$AD4") (pintype "bidirectional"))
    )
    (net (code "5") (name "DEC1") (class "Default")
      (node (ref "C5") (pin "1") (pinfunction "1_1") (pintype "passive"))
      (node (ref "U1") (pin "P$C1") (pinfunction "DEC1_P$C1") (pintype "power_in"))
    )
    (net (code "6") (name "DEC3") (class "Default")
      (node (ref "C11") (pin "1") (pinfunction "1_1") (pintype "passive"))
      (node (ref "U1") (pin "P$D23") (pinfunction "DEC3_P$D23") (pintype "bidirectional"))
    )
    (net (code "7") (name "DEC4_6") (class "Default")
      (node (ref "C10") (pin "1") (pinfunction "1_1") (pintype "passive"))
      (node (ref "C15") (pin "1") (pinfunction "1_1") (pintype "passive"))
      (node (ref "C16") (pin "1") (pinfunction "1_1") (pintype "passive"))
      (node (ref "L3") (pin "2") (pinfunction "2_2") (pintype "passive"))
      (node (ref "U1") (pin "P$B5") (pinfunction "DEC4_P$B5") (pintype "power_in"))
      (node (ref "U1") (pin "P$E24") (pinfunction "DEC6_P$E24") (pintype "bidirectional"))
    )
    (net (code "8") (name "DN") (class "Default")
      (node (ref "D3") (pin "1") (pinfunction "I/O1_1_1") (pintype "bidirectional"))
      (node (ref "J4") (pin "A7") (pinfunction "DN1_A7") (pintype "bidirectional"))
      (node (ref "J4") (pin "B7") (pinfunction "DN2_B7") (pintype "bidirectional"))
    )
    (net (code "9") (name "DP") (class "Default")
      (node (ref "D3") (pin "3") (pinfunction "I/O2_1_3") (pintype "bidirectional"))
      (node (ref "J4") (pin "A6") (pinfunction "DP1_A6") (pintype "bidirectional"))
      (node (ref "J4") (pin "B6") (pinfunction "DP2_B6") (pintype "bidirectional"))
    )
    (net (code "10") (name "EPD_3V3") (class "Default")
      (node (ref "C1-EP-DR") (pin "1") (pinfunction "1_1") (pintype "passive"))
      (node (ref "EPD_C5") (pin "2") (pinfunction "2_2") (pintype "passive"))
      (node (ref "J1") (pin "15") (pinfunction "15_15") (pintype "bidirectional"))
      (node (ref "J1") (pin "16") (pinfunction "16_16") (pintype "bidirectional"))
      (node (ref "L5") (pin "1") (pinfunction "1_1") (pintype "passive"))
      (node (ref "Q1") (pin "3") (pinfunction "D_3") (pintype "bidirectional"))
    )
    (net (code "11") (name "EPD_BUSY") (class "Default")
      (node (ref "J1") (pin "9") (pinfunction "9_9") (pintype "bidirectional"))
      (node (ref "U1") (pin "P$AD12") (pinfunction "P0.17_P$AD12") (pintype "bidirectional"))
    )
    (net (code "12") (name "EPD_CS") (class "Default")
      (node (ref "J1") (pin "12") (pinfunction "12_12") (pintype "bidirectional"))
      (node (ref "U1") (pin "P$K2") (pinfunction "P0.05/AIN3_P$K2") (pintype "bidirectional"))
    )
    (net (code "13") (name "EPD_DC") (class "Default")
      (node (ref "J1") (pin "11") (pinfunction "11_11") (pintype "bidirectional"))
      (node (ref "U1") (pin "P$AD10") (pinfunction "P0.15_P$AD10") (pintype "bidirectional"))
    )
    (net (code "14") (name "EPD_RST") (class "Default")
      (node (ref "J1") (pin "10") (pinfunction "10_10") (pintype "bidirectional"))
      (node (ref "U1") (pin "P$AC11") (pinfunction "P0.16_P$AC11") (pintype "bidirectional"))
    )
    (net (code "15") (name "GDR") (class "Default")
      (node (ref "J1") (pin "2") (pinfunction "2_2") (pintype "bidirectional"))
      (node (ref "Q3") (pin "1") (pinfunction "G_1") (pintype "bidirectional"))
      (node (ref "R2_EP_DR") (pin "2") (pinfunction "2_2") (pintype "bidirectional"))
    )
    (net (code "16") (name "GND") (class "Default")
      (node (ref "C1") (pin "2") (pinfunction "2_2") (pintype "passive"))
      (node (ref "C1-EP-DR") (pin "2") (pinfunction "2_2") (pintype "passive"))
      (node (ref "C10") (pin "2") (pinfunction "2_2") (pintype "passive"))
      (node (ref "C11") (pin "2") (pinfunction "2_2") (pintype "passive"))
      (node (ref "C12") (pin "2") (pinfunction "2_2") (pintype "passive"))
      (node (ref "C13") (pin "2") (pinfunction "2_2") (pintype "passive"))
      (node (ref "C14") (pin "2") (pinfunction "2_2") (pintype "passive"))
      (node (ref "C15") (pin "2") (pinfunction "2_2") (pintype "passive"))
      (node (ref "C16") (pin "2") (pinfunction "2_2") (pintype "passive"))
      (node (ref "C17") (pin "1") (pinfunction "1_1") (pintype "passive"))
      (node (ref "C18") (pin "1") (pinfunction "1_1") (pintype "passive"))
      (node (ref "C19") (pin "2") (pinfunction "2_2") (pintype "passive"))
      (node (ref "C2") (pin "2") (pinfunction "2_2") (pintype "passive"))
      (node (ref "C20") (pin "2") (pinfunction "2_2") (pintype "passive"))
      (node (ref "C21") (pin "2") (pinfunction "2_2") (pintype "passive"))
      (node (ref "C22") (pin "2") (pinfunction "2_2") (pintype "passive"))
      (node (ref "C23") (pin "1") (pinfunction "1_1") (pintype "passive"))
      (node (ref "C24") (pin "1") (pinfunction "1_1") (pintype "passive"))
      (node (ref "C25") (pin "2") (pinfunction "2_2") (pintype "passive"))
      (node (ref "C27") (pin "1") (pinfunction "1_1") (pintype "passive"))
      (node (ref "C29") (pin "1") (pinfunction "1_1") (pintype "passive"))
      (node (ref "C3") (pin "2") (pinfunction "2_2") (pintype "passive"))
      (node (ref "C30") (pin "1") (pinfunction "1_1") (pintype "passive"))
      (node (ref "C31") (pin "1") (pinfunction "1_1") (pintype "passive"))
      (node (ref "C32") (pin "1") (pinfunction "1_1") (pintype "passive"))
      (node (ref "C33") (pin "2") (pinfunction "2_2") (pintype "passive"))
      (node (ref "C34") (pin "1") (pinfunction "1_1") (pintype "passive"))
      (node (ref "C37") (pin "1") (pinfunction "1_1") (pintype "passive"))
      (node (ref "C38") (pin "1") (pinfunction "1_1") (pintype "passive"))
      (node (ref "C39") (pin "2") (pinfunction "2_2") (pintype "passive"))
      (node (ref "C4") (pin "2") (pinfunction "2_2") (pintype "passive"))
      (node (ref "C42") (pin "2") (pinfunction "2_2") (pintype "passive"))
      (node (ref "C43") (pin "2") (pinfunction "2_2") (pintype "passive"))
      (node (ref "C5") (pin "2") (pinfunction "2_2") (pintype "passive"))
      (node (ref "C6") (pin "2") (pinfunction "2_2") (pintype "passive"))
      (node (ref "C7") (pin "2") (pinfunction "2_2") (pintype "passive"))
      (node (ref "C8") (pin "2") (pinfunction "2_2") (pintype "passive"))
      (node (ref "C9") (pin "2") (pinfunction "2_2") (pintype "passive"))
      (node (ref "D3") (pin "2") (pinfunction "GND_2") (pintype "bidirectional"))
      (node (ref "D4") (pin "1") (pinfunction "K_1") (pintype "bidirectional"))
      (node (ref "EPD_C1") (pin "1") (pinfunction "1_1") (pintype "passive"))
      (node (ref "EPD_C10") (pin "1") (pinfunction "1_1") (pintype "passive"))
      (node (ref "EPD_C11") (pin "1") (pinfunction "1_1") (pintype "passive"))
      (node (ref "EPD_C12") (pin "1") (pinfunction "1_1") (pintype "passive"))
      (node (ref "EPD_C2") (pin "1") (pinfunction "1_1") (pintype "passive"))
      (node (ref "EPD_C5") (pin "1") (pinfunction "1_1") (pintype "passive"))
      (node (ref "EPD_C6") (pin "1") (pinfunction "1_1") (pintype "passive"))
      (node (ref "EPD_C7") (pin "1") (pinfunction "1_1") (pintype "passive"))
      (node (ref "EPD_C8") (pin "1") (pinfunction "1_1") (pintype "passive"))
      (node (ref "EPD_C9") (pin "1") (pinfunction "1_1") (pintype "passive"))
      (node (ref "IC1") (pin "D2") (pinfunction "GND_D2") (pintype "bidirectional"))
      (node (ref "IC2") (pin "B1") (pinfunction "IN/TRIG_B1") (pintype "bidirectional"))
      (node (ref "IC2") (pin "B3") (pinfunction "GND_B3") (pintype "bidirectional"))
      (node (ref "IC3") (pin "8") (pinfunction "GNDIO_8") (pintype "bidirectional"))
      (node (ref "IC3") (pin "9") (pinfunction "GND_9") (pintype "bidirectional"))
      (node (ref "IC9") (pin "B1") (pinfunction "VSEL_B1") (pintype "bidirectional"))
      (node (ref "IC9") (pin "C1") (pinfunction "AGND_C1") (pintype "bidirectional"))
      (node (ref "IC9") (pin "C2") (pinfunction "PGND_1_C2") (pintype "bidirectional"))
      (node (ref "IC9") (pin "C3") (pinfunction "PGND_2_C3") (pintype "bidirectional"))
      (node (ref "J1") (pin "17") (pinfunction "17_17") (pintype "bidirectional"))
      (node (ref "J1") (pin "8") (pinfunction "8_8") (pintype "bidirectional"))
      (node (ref "J1") (pin "MP1") (pinfunction "MP1_MP1") (pintype "bidirectional"))
      (node (ref "J1") (pin "MP2") (pinfunction "MP2_MP2") (pintype "bidirectional"))
      (node (ref "J2") (pin "3") (pinfunction "3_3") (pintype "bidirectional"))
      (node (ref "J2") (pin "5") (pinfunction "5_5") (pintype "bidirectional"))
      (node (ref "J4") (pin "A12_B1") (pinfunction "GND_A12_B1") (pintype "power_in"))
      (node (ref "J4") (pin "A1_B12") (pinfunction "GND_A1_B12") (pintype "power_in"))
      (node (ref "J4") (pin "SH1") (pinfunction "SHIELD_SH1") (pintype "passive"))
      (node (ref "J4") (pin "SH2") (pinfunction "SHIELD_SH2") (pintype "passive"))
      (node (ref "J4") (pin "SH3") (pinfunction "SHIELD_SH3") (pintype "passive"))
      (node (ref "J4") (pin "SH4") (pinfunction "SHIELD_SH4") (pintype "passive"))
      (node (ref "R1_USB") (pin "1") (pinfunction "1_1") (pintype "bidirectional"))
      (node (ref "R2_EP_DR") (pin "1") (pinfunction "1_1") (pintype "bidirectional"))
      (node (ref "R2_USB") (pin "2") (pinfunction "2_2") (pintype "bidirectional"))
      (node (ref "R3") (pin "1") (pinfunction "1_1") (pintype "bidirectional"))
      (node (ref "R9") (pin "1") (pinfunction "1_1") (pintype "bidirectional"))
      (node (ref "R_TYPE_SEL") (pin "1") (pinfunction "1_1") (pintype "bidirectional"))
      (node (ref "SJ1") (pin "1") (pinfunction "1_1") (pintype "passive"))
      (node (ref "SW_DN") (pin "1") (pinfunction "1_1") (pintype "passive"))
      (node (ref "SW_ENT") (pin "1") (pinfunction "1_1") (pintype "passive"))
      (node (ref "SW_UP") (pin "1") (pinfunction "1_1") (pintype "passive"))
      (node (ref "TP_BAT_GND") (pin "TP") (pinfunction "TP_TP") (pintype "input"))
      (node (ref "TP_GND") (pin "TP") (pinfunction "TP_TP") (pintype "input"))
      (node (ref "U1") (pin "P$74") (pinfunction "VSS_PAD_P$74") (pintype "bidirectional"))
      (node (ref "U1") (pin "P$75") (pinfunction "VSS_PAD_P$75") (pintype "bidirectional"))
      (node (ref "U1") (pin "P$76") (pinfunction "VSS_PAD_P$76") (pintype "bidirectional"))
      (node (ref "U1") (pin "P$77") (pinfunction "VSS_PAD_P$77") (pintype "bidirectional"))
      (node (ref "U1") (pin "P$78") (pinfunction "VSS_PAD_P$78") (pintype "bidirectional"))
      (node (ref "U1") (pin "P$79") (pinfunction "VSS_PAD_P$79") (pintype "bidirectional"))
      (node (ref "U1") (pin "P$80") (pinfunction "VSS_PAD_P$80") (pintype "bidirectional"))
      (node (ref "U1") (pin "P$81") (pinfunction "VSS_PAD_P$81") (pintype "bidirectional"))
      (node (ref "U1") (pin "P$82") (pinfunction "VSS_PAD_P$82") (pintype "bidirectional"))
      (node (ref "U1") (pin "P$83") (pinfunction "VSS_PAD_P$83") (pintype "bidirectional"))
      (node (ref "U1") (pin "P$84") (pinfunction "VSS_PAD_P$84") (pintype "bidirectional"))
      (node (ref "U1") (pin "P$85") (pinfunction "VSS_PAD_P$85") (pintype "bidirectional"))
      (node (ref "U1") (pin "P$86") (pinfunction "VSS_PAD_P$86") (pintype "bidirectional"))
      (node (ref "U1") (pin "P$87") (pinfunction "VSS_PAD_P$87") (pintype "bidirectional"))
      (node (ref "U1") (pin "P$88") (pinfunction "VSS_PAD_P$88") (pintype "bidirectional"))
      (node (ref "U1") (pin "P$89") (pinfunction "VSS_PAD_P$89") (pintype "bidirectional"))
      (node (ref "U1") (pin "P$90") (pinfunction "VSS_PAD_P$90") (pintype "bidirectional"))
      (node (ref "U1") (pin "P$B7") (pinfunction "VSS_P$B7") (pintype "power_in"))
      (node (ref "U1") (pin "P$F23") (pinfunction "VSS_PA_P$F23") (pintype "bidirectional"))
      (node (ref "U3") (pin "1") (pinfunction "CTG_1") (pintype "power_in"))
      (node (ref "U3") (pin "4") (pinfunction "GND_4") (pintype "power_in"))
      (node (ref "U3") (pin "6") (pinfunction "QSTRT_6") (pintype "input"))
      (node (ref "U3") (pin "9") (pinfunction "EP_9") (pintype "power_in"))
      (node (ref "X1") (pin "2") (pinfunction "2_2") (pintype "passive"))
      (node (ref "X1") (pin "4") (pinfunction "4_4") (pintype "passive"))
    )
    (net (code "17") (name "HAPTIC_EN") (class "Default")
      (node (ref "IC2") (pin "A1") (pinfunction "EN_A1") (pintype "bidirectional"))
      (node (ref "U1") (pin "P$U1") (pinfunction "P0.12_P$U1") (pintype "bidirectional"))
    )
    (net (code "18") (name "IMU_INT1") (class "Default")
      (node (ref "IC3") (pin "5") (pinfunction "INT1_5") (pintype "bidirectional"))
      (node (ref "U1") (pin "P$N1") (pinfunction "P0.08_P$N1") (pintype "bidirectional"))
    )
    (net (code "19") (name "IMU_INT2") (class "Default")
      (node (ref "IC3") (pin "6") (pinfunction "INT2_6") (pintype "bidirectional"))
      (node (ref "U1") (pin "P$P2") (pinfunction "P1.08_P$P2") (pintype "bidirectional"))
    )
    (net (code "20") (name "LX1") (class "Default")
      (node (ref "IC9") (pin "B2") (pinfunction "SW1_1_B2") (pintype "bidirectional"))
      (node (ref "IC9") (pin "B3") (pinfunction "SW1_2_B3") (pintype "bidirectional"))
      (node (ref "L7") (pin "1") (pinfunction "1_1") (pintype "bidirectional"))
    )
    (net (code "21") (name "LX2") (class "Default")
      (node (ref "IC9") (pin "D2") (pinfunction "SW2_1_D2") (pintype "bidirectional"))
      (node (ref "IC9") (pin "D3") (pinfunction "SW2_2_D3") (pintype "bidirectional"))
      (node (ref "L7") (pin "2") (pinfunction "2_2") (pintype "bidirectional"))
    )
    (net (code "22") (name "MOSI") (class "Default")
      (node (ref "J1") (pin "14") (pinfunction "14_14") (pintype "bidirectional"))
      (node (ref "U1") (pin "P$B13") (pinfunction "P0.03/AIN1_P$B13") (pintype "bidirectional"))
    )
    (net (code "23") (name "Net-(D2-K)") (class "Default")
      (node (ref "C2-EP-DR") (pin "1") (pinfunction "1_1") (pintype "passive"))
      (node (ref "D2") (pin "1") (pinfunction "K_1") (pintype "bidirectional"))
      (node (ref "D4") (pin "2") (pinfunction "A_2") (pintype "bidirectional"))
      (node (ref "Q3") (pin "3") (pinfunction "D_3") (pintype "bidirectional"))
    )
    (net (code "24") (name "Net-(D5-A)") (class "Default")
      (node (ref "C2-EP-DR") (pin "2") (pinfunction "2_2") (pintype "passive"))
      (node (ref "D5") (pin "2") (pinfunction "A_2") (pintype "bidirectional"))
      (node (ref "L5") (pin "2") (pinfunction "2_2") (pintype "passive"))
    )
    (net (code "25") (name "Net-(EPD_C1-Pad2)") (class "Default")
      (node (ref "EPD_C1") (pin "2") (pinfunction "2_2") (pintype "passive"))
      (node (ref "J1") (pin "5") (pinfunction "5_5") (pintype "bidirectional"))
    )
    (net (code "26") (name "Net-(EPD_C2-Pad2)") (class "Default")
      (node (ref "EPD_C2") (pin "2") (pinfunction "2_2") (pintype "passive"))
      (node (ref "J1") (pin "4") (pinfunction "4_4") (pintype "bidirectional"))
    )
    (net (code "27") (name "Net-(EPD_C6-Pad2)") (class "Default")
      (node (ref "EPD_C6") (pin "2") (pinfunction "2_2") (pintype "passive"))
      (node (ref "J1") (pin "18") (pinfunction "18_18") (pintype "bidirectional"))
    )
    (net (code "28") (name "Net-(EPD_C7-Pad2)") (class "Default")
      (node (ref "EPD_C7") (pin "2") (pinfunction "2_2") (pintype "passive"))
      (node (ref "J1") (pin "19") (pinfunction "19_19") (pintype "bidirectional"))
    )
    (net (code "29") (name "Net-(EPD_C8-Pad2)") (class "Default")
      (node (ref "EPD_C8") (pin "2") (pinfunction "2_2") (pintype "passive"))
      (node (ref "J1") (pin "20") (pinfunction "20_20") (pintype "bidirectional"))
    )
    (net (code "30") (name "Net-(EPD_C9-Pad2)") (class "Default")
      (node (ref "EPD_C9") (pin "2") (pinfunction "2_2") (pintype "passive"))
      (node (ref "J1") (pin "21") (pinfunction "21_21") (pintype "bidirectional"))
    )
    (net (code "31") (name "Net-(EPD_C10-Pad2)") (class "Default")
      (node (ref "EPD_C10") (pin "2") (pinfunction "2_2") (pintype "passive"))
      (node (ref "J1") (pin "22") (pinfunction "22_22") (pintype "bidirectional"))
    )
    (net (code "32") (name "Net-(IC1-TS{slash}MR)") (class "Default")
      (node (ref "IC1") (pin "D1") (pinfunction "TS/MR_D1") (pintype "bidirectional"))
      (node (ref "R9") (pin "2") (pinfunction "2_2") (pintype "bidirectional"))
    )
    (net (code "33") (name "Net-(IC2-REG)") (class "Default")
      (node (ref "C32") (pin "2") (pinfunction "2_2") (pintype "passive"))
      (node (ref "IC2") (pin "A2") (pinfunction "REG_A2") (pintype "bidirectional"))
    )
    (net (code "34") (name "Net-(IC3-SDO)") (class "Default")
      (node (ref "IC3") (pin "1") (pinfunction "SDO_1") (pintype "bidirectional"))
      (node (ref "R3") (pin "2") (pinfunction "2_2") (pintype "bidirectional"))
    )
    (net (code "35") (name "Net-(IC9-SCL)") (class "Default")
      (node (ref "IC9") (pin "D1") (pinfunction "SCL_D1") (pintype "bidirectional"))
      (node (ref "R4") (pin "2") (pinfunction "2_2") (pintype "bidirectional"))
    )
    (net (code "36") (name "Net-(IC9-SDA)") (class "Default")
      (node (ref "IC9") (pin "E1") (pinfunction "SDA_E1") (pintype "bidirectional"))
      (node (ref "R2") (pin "2") (pinfunction "2_2") (pintype "bidirectional"))
    )
    (net (code "37") (name "Net-(J4-CC1)") (class "Default")
      (node (ref "J4") (pin "A5") (pinfunction "CC1_A5") (pintype "bidirectional"))
      (node (ref "R1_USB") (pin "2") (pinfunction "2_2") (pintype "bidirectional"))
    )
    (net (code "38") (name "Net-(J4-CC2)") (class "Default")
      (node (ref "J4") (pin "B5") (pinfunction "CC2_B5") (pintype "bidirectional"))
      (node (ref "R2_USB") (pin "1") (pinfunction "1_1") (pintype "bidirectional"))
    )
    (net (code "39") (name "Net-(L2-Pad2)") (class "Default")
      (node (ref "L2") (pin "2") (pinfunction "2_2") (pintype "passive"))
      (node (ref "L3") (pin "1") (pinfunction "1_1") (pintype "passive"))
    )
    (net (code "40") (name "Net-(R1_EP_DR-Pad1)") (class "Default")
      (node (ref "R1_EP_DR") (pin "1") (pinfunction "1_1") (pintype "bidirectional"))
      (node (ref "R_TYPE_SEL") (pin "2") (pinfunction "2_2") (pintype "bidirectional"))
      (node (ref "SJ1") (pin "2") (pinfunction "2_2") (pintype "passive"))
    )
    (net (code "41") (name "Net-(U1-ANT)") (class "Default")
      (node (ref "C3") (pin "1") (pinfunction "1_1") (pintype "passive"))
      (node (ref "L1") (pin "1") (pinfunction "1_1") (pintype "passive"))
      (node (ref "U1") (pin "P$H23") (pinfunction "ANT_P$H23") (pintype "bidirectional"))
    )
    (net (code "42") (name "Net-(U1-DCC)") (class "Default")
      (node (ref "L2") (pin "1") (pinfunction "1_1") (pintype "passive"))
      (node (ref "U1") (pin "P$B3") (pinfunction "DCC_P$B3") (pintype "output"))
    )
    (net (code "43") (name "Net-(U1-DEC2)") (class "Default")
      (node (ref "C13") (pin "1") (pinfunction "1_1") (pintype "passive"))
      (node (ref "U1") (pin "P$A18") (pinfunction "DEC2_P$A18") (pintype "bidirectional"))
    )
    (net (code "44") (name "Net-(U1-DEC3V3)") (class "Default")
      (node (ref "C20") (pin "1") (pinfunction "1_1") (pintype "passive"))
      (node (ref "U1") (pin "P$AC5") (pinfunction "DEC3V3_P$AC5") (pintype "bidirectional"))
    )
    (net (code "45") (name "Net-(U1-DEC5)") (class "Default")
      (node (ref "C9") (pin "1") (pinfunction "1_1") (pintype "passive"))
      (node (ref "U1") (pin "P$N24") (pinfunction "DEC5_P$N24") (pintype "bidirectional"))
    )
    (net (code "46") (name "Net-(U1-XC1)") (class "Default")
      (node (ref "C1") (pin "1") (pinfunction "1_1") (pintype "passive"))
      (node (ref "U1") (pin "P$B24") (pinfunction "XC1_P$B24") (pintype "input"))
      (node (ref "X1") (pin "1") (pinfunction "1_1") (pintype "passive"))
    )
    (net (code "47") (name "Net-(U1-XC2)") (class "Default")
      (node (ref "C2") (pin "1") (pinfunction "1_1") (pintype "passive"))
      (node (ref "U1") (pin "P$A23") (pinfunction "XC2_P$A23") (pintype "output"))
      (node (ref "X1") (pin "3") (pinfunction "3_3") (pintype "passive"))
    )
    (net (code "48") (name "OUT+") (class "Default")
      (node (ref "IC2") (pin "A3") (pinfunction "OUT+_A3") (pintype "bidirectional"))
      (node (ref "TP_OP") (pin "TP") (pinfunction "TP_TP") (pintype "input"))
    )
    (net (code "49") (name "OUT-") (class "Default")
      (node (ref "IC2") (pin "C3") (pinfunction "OUT-_C3") (pintype "bidirectional"))
      (node (ref "TP_ON") (pin "TP") (pinfunction "TP_TP") (pintype "input"))
    )
    (net (code "50") (name "P0.00{slash}XL1") (class "Default")
      (node (ref "C17") (pin "2") (pinfunction "2_2") (pintype "passive"))
      (node (ref "U1") (pin "P$D2") (pinfunction "P0.00/XL1_P$D2") (pintype "bidirectional"))
      (node (ref "X2") (pin "1") (pinfunction "1_1") (pintype "passive"))
    )
    (net (code "51") (name "P0.01{slash}XL2") (class "Default")
      (node (ref "C18") (pin "2") (pinfunction "2_2") (pintype "passive"))
      (node (ref "U1") (pin "P$F2") (pinfunction "P0.01/XL2_P$F2") (pintype "bidirectional"))
      (node (ref "X2") (pin "2") (pinfunction "2_2") (pintype "passive"))
    )
    (net (code "52") (name "P0.04") (class "Default")
      (node (ref "U1") (pin "P$J1") (pinfunction "P0.04/AIN2_P$J1") (pintype "bidirectional"))
    )
    (net (code "53") (name "P0.09") (class "Default")
      (node (ref "U1") (pin "P$L24") (pinfunction "P0.09/NFC1_P$L24") (pintype "bidirectional"))
    )
    (net (code "54") (name "P0.13") (class "Default")
      (node (ref "C30") (pin "2") (pinfunction "2_2") (pintype "passive"))
      (node (ref "R5") (pin "1") (pinfunction "1_1") (pintype "bidirectional"))
      (node (ref "SW_UP") (pin "2") (pinfunction "2_2") (pintype "passive"))
      (node (ref "U1") (pin "P$AD8") (pinfunction "P0.13_P$AD8") (pintype "bidirectional"))
    )
    (net (code "55") (name "P0.14") (class "Default")
      (node (ref "C31") (pin "2") (pinfunction "2_2") (pintype "passive"))
      (node (ref "R8") (pin "1") (pinfunction "1_1") (pintype "bidirectional"))
      (node (ref "SW_ENT") (pin "2") (pinfunction "2_2") (pintype "passive"))
      (node (ref "U1") (pin "P$AC9") (pinfunction "P0.14_P$AC9") (pintype "bidirectional"))
    )
    (net (code "56") (name "P0.19") (class "Default")
      (node (ref "U1") (pin "P$AC15") (pinfunction "P0.19_P$AC15") (pintype "bidirectional"))
    )
    (net (code "57") (name "P0.20") (class "Default")
      (node (ref "U1") (pin "P$AD16") (pinfunction "P0.20_P$AD16") (pintype "bidirectional"))
    )
    (net (code "58") (name "P0.21") (class "Default")
      (node (ref "U1") (pin "P$AC17") (pinfunction "P0.21_P$AC17") (pintype "bidirectional"))
    )
    (net (code "59") (name "P0.22") (class "Default")
      (node (ref "U1") (pin "P$AD18") (pinfunction "P0.22_P$AD18") (pintype "bidirectional"))
    )
    (net (code "60") (name "P0.23") (class "Default")
      (node (ref "U1") (pin "P$AC19") (pinfunction "P0.23_P$AC19") (pintype "bidirectional"))
    )
    (net (code "61") (name "P0.24") (class "Default")
      (node (ref "U1") (pin "P$AD20") (pinfunction "P0.24_P$AD20") (pintype "bidirectional"))
    )
    (net (code "62") (name "P0.25") (class "Default")
      (node (ref "U1") (pin "P$AC21") (pinfunction "P0.25_P$AC21") (pintype "bidirectional"))
    )
    (net (code "63") (name "P0.26") (class "Default")
      (node (ref "U1") (pin "P$G1") (pinfunction "P0.26_P$G1") (pintype "bidirectional"))
    )
    (net (code "64") (name "P0.27") (class "Default")
      (node (ref "U1") (pin "P$H2") (pinfunction "P0.27_P$H2") (pintype "bidirectional"))
    )
    (net (code "65") (name "P0.28") (class "Default")
      (node (ref "U1") (pin "P$B11") (pinfunction "P0.28/AIN4_P$B11") (pintype "bidirectional"))
    )
    (net (code "66") (name "P0.29") (class "Default")
      (node (ref "U1") (pin "P$A10") (pinfunction "P0.29/AIN5_P$A10") (pintype "bidirectional"))
    )
    (net (code "67") (name "P0.30") (class "Default")
      (node (ref "U1") (pin "P$B9") (pinfunction "P0.30/AIN6_P$B9") (pintype "bidirectional"))
    )
    (net (code "68") (name "P0.31") (class "Default")
      (node (ref "U1") (pin "P$A8") (pinfunction "P0.31/AIN7_P$A8") (pintype "bidirectional"))
    )
    (net (code "69") (name "P1.01") (class "Default")
      (node (ref "Q1") (pin "1") (pinfunction "G_1") (pintype "bidirectional"))
      (node (ref "R_PWR_EPD") (pin "1") (pinfunction "1_1") (pintype "bidirectional"))
      (node (ref "U1") (pin "P$Y23") (pinfunction "P1.01_P$Y23") (pintype "bidirectional"))
    )
    (net (code "70") (name "P1.02") (class "Default")
      (node (ref "C29") (pin "2") (pinfunction "2_2") (pintype "passive"))
      (node (ref "R7") (pin "1") (pinfunction "1_1") (pintype "bidirectional"))
      (node (ref "SW_DN") (pin "2") (pinfunction "2_2") (pintype "passive"))
      (node (ref "U1") (pin "P$W24") (pinfunction "P1.02_P$W24") (pintype "bidirectional"))
    )
    (net (code "71") (name "P1.03") (class "Default")
      (node (ref "U1") (pin "P$V23") (pinfunction "P1.03_P$V23") (pintype "bidirectional"))
    )
    (net (code "72") (name "P1.04") (class "Default")
      (node (ref "U1") (pin "P$U24") (pinfunction "P1.04_P$U24") (pintype "bidirectional"))
    )
    (net (code "73") (name "P1.05") (class "Default")
      (node (ref "U1") (pin "P$T23") (pinfunction "P1.05_P$T23") (pintype "bidirectional"))
    )
    (net (code "74") (name "P1.06") (class "Default")
      (node (ref "U1") (pin "P$R24") (pinfunction "P1.06_P$R24") (pintype "bidirectional"))
    )
    (net (code "75") (name "P1.07") (class "Default")
      (node (ref "U1") (pin "P$P23") (pinfunction "P1.07_P$P23") (pintype "bidirectional"))
    )
    (net (code "76") (name "P1.09") (class "Default")
      (node (ref "U1") (pin "P$R1") (pinfunction "P1.09_P$R1") (pintype "bidirectional"))
    )
    (net (code "77") (name "P1.10") (class "Default")
      (node (ref "U1") (pin "P$A20") (pinfunction "P1.10_P$A20") (pintype "bidirectional"))
    )
    (net (code "78") (name "P1.11") (class "Default")
      (node (ref "U1") (pin "P$B19") (pinfunction "P1.11_P$B19") (pintype "bidirectional"))
    )
    (net (code "79") (name "P1.12") (class "Default")
      (node (ref "U1") (pin "P$B17") (pinfunction "P1.12_P$B17") (pintype "bidirectional"))
    )
    (net (code "80") (name "P1.13") (class "Default")
      (node (ref "U1") (pin "P$A16") (pinfunction "P1.13_P$A16") (pintype "bidirectional"))
    )
    (net (code "81") (name "P1.14") (class "Default")
      (node (ref "U1") (pin "P$B15") (pinfunction "P1.14_P$B15") (pintype "bidirectional"))
    )
    (net (code "82") (name "P1.15") (class "Default")
      (node (ref "U1") (pin "P$A14") (pinfunction "P1.15_P$A14") (pintype "bidirectional"))
    )
    (net (code "83") (name "PMIC_INT") (class "Default")
      (node (ref "IC1") (pin "A1") (pinfunction "~{INT}_A1") (pintype "bidirectional"))
      (node (ref "U1") (pin "P$T2") (pinfunction "P0.11_P$T2") (pintype "bidirectional"))
    )
    (net (code "84") (name "PREVGH") (class "Default")
      (node (ref "D5") (pin "1") (pinfunction "K_1") (pintype "bidirectional"))
      (node (ref "EPD_C12") (pin "2") (pinfunction "2_2") (pintype "passive"))
      (node (ref "J1") (pin "24") (pinfunction "24_24") (pintype "bidirectional"))
    )
    (net (code "85") (name "PREVGL") (class "Default")
      (node (ref "D2") (pin "2") (pinfunction "A_2") (pintype "bidirectional"))
      (node (ref "EPD_C11") (pin "2") (pinfunction "2_2") (pintype "passive"))
      (node (ref "J1") (pin "23") (pinfunction "23_23") (pintype "bidirectional"))
    )
    (net (code "86") (name "RESE") (class "Default")
      (node (ref "J1") (pin "3") (pinfunction "3_3") (pintype "bidirectional"))
      (node (ref "Q3") (pin "2") (pinfunction "S_2") (pintype "bidirectional"))
      (node (ref "R1_EP_DR") (pin "2") (pinfunction "2_2") (pintype "bidirectional"))
    )
    (net (code "87") (name "RESET") (class "Default")
      (node (ref "J2") (pin "6") (pinfunction "6_6") (pintype "bidirectional"))
      (node (ref "TP_RESET") (pin "TP") (pinfunction "TP_TP") (pintype "input"))
      (node (ref "U1") (pin "P$AC13") (pinfunction "P0.18/RESET_P$AC13") (pintype "bidirectional"))
    )
    (net (code "88") (name "RF") (class "Default")
      (node (ref "ANT1") (pin "1") (pinfunction "FEED_1") (pintype "input"))
      (node (ref "C22") (pin "1") (pinfunction "1_1") (pintype "passive"))
      (node (ref "C4") (pin "1") (pinfunction "1_1") (pintype "passive"))
      (node (ref "L1") (pin "2") (pinfunction "2_2") (pintype "passive"))
    )
    (net (code "89") (name "SCK") (class "Default")
      (node (ref "J1") (pin "13") (pinfunction "13_13") (pintype "bidirectional"))
      (node (ref "U1") (pin "P$A12") (pinfunction "P0.02/AIN0_P$A12") (pintype "bidirectional"))
    )
    (net (code "90") (name "SCL") (class "Default")
      (node (ref "IC1") (pin "B1") (pinfunction "SCL_B1") (pintype "bidirectional"))
      (node (ref "IC2") (pin "C1") (pinfunction "SCL_C1") (pintype "bidirectional"))
      (node (ref "IC3") (pin "12") (pinfunction "SCX_12") (pintype "bidirectional"))
      (node (ref "R17") (pin "2") (pinfunction "2_2") (pintype "bidirectional"))
      (node (ref "R4") (pin "1") (pinfunction "1_1") (pintype "bidirectional"))
      (node (ref "TP_SCL") (pin "TP") (pinfunction "TP_TP") (pintype "input"))
      (node (ref "U1") (pin "P$M2") (pinfunction "P0.07_P$M2") (pintype "bidirectional"))
      (node (ref "U3") (pin "7") (pinfunction "SCL_7") (pintype "input"))
    )
    (net (code "91") (name "SDA") (class "Default")
      (node (ref "IC1") (pin "C1") (pinfunction "SDA_C1") (pintype "bidirectional"))
      (node (ref "IC2") (pin "B2") (pinfunction "SDA_B2") (pintype "bidirectional"))
      (node (ref "IC3") (pin "2") (pinfunction "SDX_2") (pintype "bidirectional"))
      (node (ref "R18") (pin "2") (pinfunction "2_2") (pintype "bidirectional"))
      (node (ref "R2") (pin "1") (pinfunction "1_1") (pintype "bidirectional"))
      (node (ref "TP_SDA") (pin "TP") (pinfunction "TP_TP") (pintype "input"))
      (node (ref "U1") (pin "P$L1") (pinfunction "P0.06_P$L1") (pintype "bidirectional"))
      (node (ref "U3") (pin "8") (pinfunction "SDA_8") (pintype "bidirectional"))
    )
    (net (code "92") (name "SWDCLK") (class "Default")
      (node (ref "J2") (pin "4") (pinfunction "4_4") (pintype "bidirectional"))
      (node (ref "TP_SWDCLK") (pin "TP") (pinfunction "TP_TP") (pintype "input"))
      (node (ref "U1") (pin "P$AA24") (pinfunction "SWDCLK_P$AA24") (pintype "input"))
    )
    (net (code "93") (name "SWDIO") (class "Default")
      (node (ref "J2") (pin "2") (pinfunction "2_2") (pintype "bidirectional"))
      (node (ref "TP_SWDIO") (pin "TP") (pinfunction "TP_TP") (pintype "input"))
      (node (ref "U1") (pin "P$AC24") (pinfunction "SWDIO_P$AC24") (pintype "bidirectional"))
    )
    (net (code "94") (name "SWO") (class "Default")
      (node (ref "TP_SWO") (pin "TP") (pinfunction "TP_TP") (pintype "input"))
      (node (ref "U1") (pin "P$AD22") (pinfunction "P1.00_P$AD22") (pintype "bidirectional"))
    )
    (net (code "95") (name "VBAT") (class "Default")
      (node (ref "C27") (pin "2") (pinfunction "2_2") (pintype "passive"))
      (node (ref "C37") (pin "2") (pinfunction "2_2") (pintype "passive"))
      (node (ref "IC1") (pin "C2") (pinfunction "BAT_C2") (pintype "bidirectional"))
      (node (ref "TP_VBAT") (pin "TP") (pinfunction "TP_TP") (pintype "input"))
      (node (ref "U3") (pin "2") (pinfunction "CELL_2") (pintype "power_in"))
      (node (ref "U3") (pin "3") (pinfunction "VDD_3") (pintype "power_in"))
    )
    (net (code "96") (name "VBUS") (class "Default")
      (node (ref "C21") (pin "1") (pinfunction "1_1") (pintype "passive"))
      (node (ref "C38") (pin "2") (pinfunction "2_2") (pintype "passive"))
      (node (ref "C42") (pin "1") (pinfunction "1_1") (pintype "passive"))
      (node (ref "C43") (pin "1") (pinfunction "1_1") (pintype "passive"))
      (node (ref "D3") (pin "5") (pinfunction "VBUS_5") (pintype "bidirectional"))
      (node (ref "IC1") (pin "A2") (pinfunction "IN_A2") (pintype "bidirectional"))
      (node (ref "J4") (pin "A4_B9") (pinfunction "VBUS_A4_B9") (pintype "power_in"))
      (node (ref "J4") (pin "A9_B4") (pinfunction "VBUS_A9_B4") (pintype "power_in"))
      (node (ref "U1") (pin "P$AD2") (pinfunction "VBUS_P$AD2") (pintype "power_in"))
    )
    (net (code "97") (name "VREG") (class "Default")
      (node (ref "C23") (pin "2") (pinfunction "2_2") (pintype "passive"))
      (node (ref "C24") (pin "2") (pinfunction "2_2") (pintype "passive"))
      (node (ref "C39") (pin "1") (pinfunction "1_1") (pintype "passive"))
      (node (ref "IC1") (pin "B2") (pinfunction "SYS_B2") (pintype "bidirectional"))
      (node (ref "IC9") (pin "A1") (pinfunction "EN_A1") (pintype "bidirectional"))
      (node (ref "IC9") (pin "A2") (pinfunction "VIN_1_A2") (pintype "bidirectional"))
      (node (ref "IC9") (pin "A3") (pinfunction "VIN_2_A3") (pintype "bidirectional"))
      (node (ref "TP_VREG") (pin "TP") (pinfunction "TP_TP") (pintype "input"))
    )
    (net (code "98") (name "unconnected-(ANT1-NC-Pad2)") (class "Default")
      (node (ref "ANT1") (pin "2") (pinfunction "NC_2") (pintype "no_connect"))
    )
    (net (code "99") (name "unconnected-(IC3-ASCL-Pad11)") (class "Default")
      (node (ref "IC3") (pin "11") (pinfunction "ASCL_11") (pintype "bidirectional"))
    )
    (net (code "100") (name "unconnected-(IC3-ASDA-Pad4)") (class "Default")
      (node (ref "IC3") (pin "4") (pinfunction "ASDA_4") (pintype "bidirectional"))
    )
    (net (code "101") (name "unconnected-(J1-Pad1)") (class "Default")
      (node (ref "J1") (pin "1") (pinfunction "1_1") (pintype "bidirectional"))
    )
    (net (code "102") (name "unconnected-(J1-Pad6)") (class "Default")
      (node (ref "J1") (pin "6") (pinfunction "6_6") (pintype "bidirectional"))
    )
    (net (code "103") (name "unconnected-(J1-Pad7)") (class "Default")
      (node (ref "J1") (pin "7") (pinfunction "7_7") (pintype "bidirectional"))
    )
    (net (code "104") (name "unconnected-(J4-SBU1-PadA8)") (class "Default")
      (node (ref "J4") (pin "A8") (pinfunction "SBU1_A8") (pintype "bidirectional"))
    )
    (net (code "105") (name "unconnected-(J4-SBU2-PadB8)") (class "Default")
      (node (ref "J4") (pin "B8") (pinfunction "SBU2_B8") (pintype "bidirectional"))
    )
    (net (code "106") (name "unconnected-(U1-DCCH-PadP$AB2)") (class "Default")
      (node (ref "U1") (pin "P$AB2") (pinfunction "DCCH_P$AB2") (pintype "bidirectional"))
    )
  )
)
